# PulseOxi.net
KiCad netlist of a schematic drawn in EAGLE
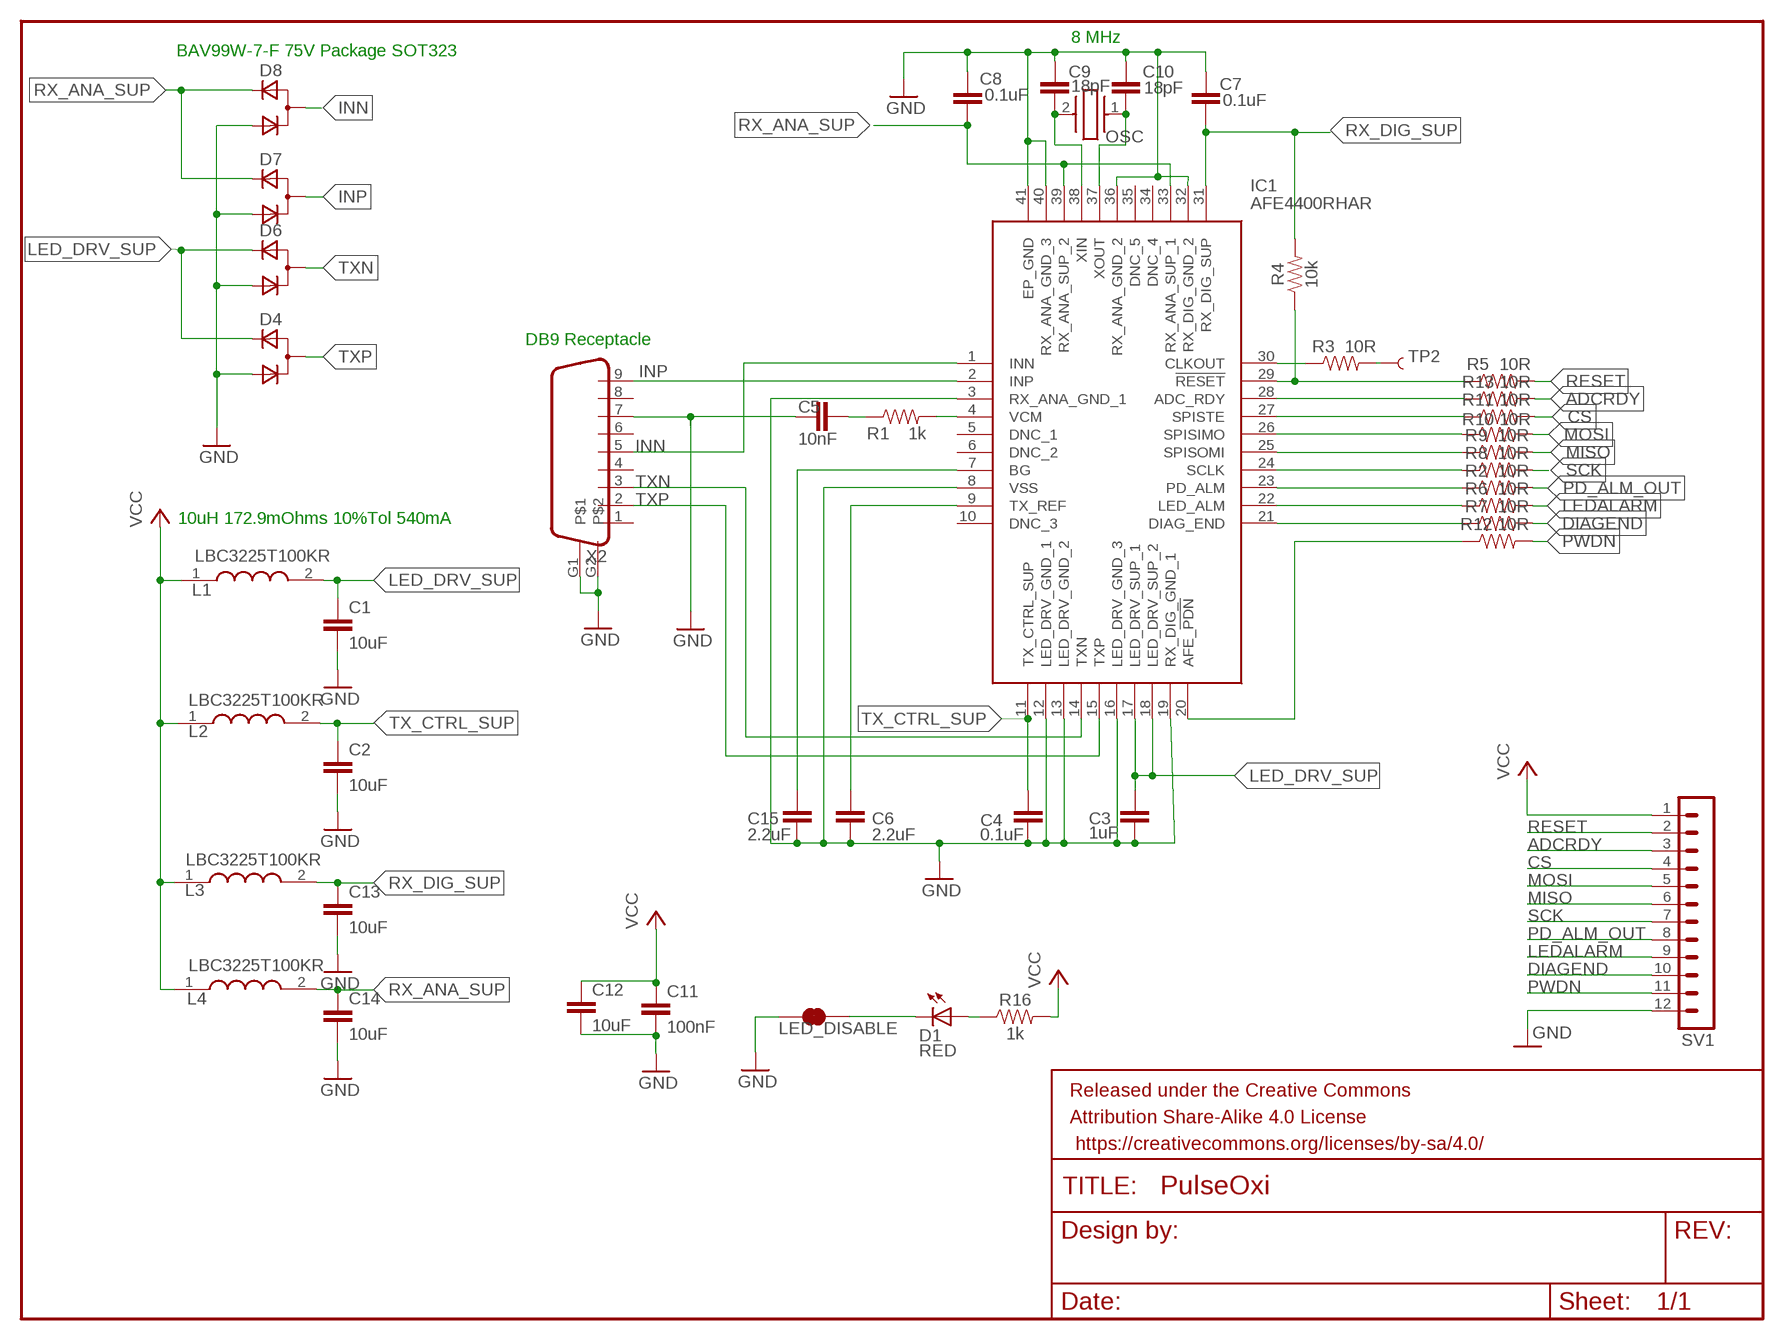
[diagram p0: schematic, sheet 1]

(export (version "E")
  (design (tool "Eeschema 10.0.6"))
  (components
    (comp (ref "C1")
      (value "10uF")
      (footprint "eagle-import:0603")
      (libsource (lib "eagle-import") (part "27PF-0603-50V-5%"))
    )
    (comp (ref "C2")
      (value "10uF")
      (footprint "eagle-import:0603")
      (libsource (lib "eagle-import") (part "27PF-0603-50V-5%"))
    )
    (comp (ref "C3")
      (value "1uF")
      (footprint "eagle-import:0603")
      (libsource (lib "eagle-import") (part "27PF-0603-50V-5%"))
    )
    (comp (ref "C4")
      (value "0.1uF")
      (footprint "eagle-import:0603")
      (libsource (lib "eagle-import") (part "27PF-0603-50V-5%"))
    )
    (comp (ref "C5")
      (value "10nF")
      (footprint "eagle-import:0603")
      (libsource (lib "eagle-import") (part "10NF-0603-50V-10%"))
    )
    (comp (ref "C6")
      (value "2.2uF")
      (footprint "eagle-import:0603")
      (libsource (lib "eagle-import") (part "27PF-0603-50V-5%"))
    )
    (comp (ref "C7")
      (value "0.1uF")
      (footprint "eagle-import:0603")
      (libsource (lib "eagle-import") (part "27PF-0603-50V-5%"))
    )
    (comp (ref "C8")
      (value "0.1uF")
      (footprint "eagle-import:0603")
      (libsource (lib "eagle-import") (part "27PF-0603-50V-5%"))
    )
    (comp (ref "C9")
      (value "18pF")
      (footprint "eagle-import:0603")
      (libsource (lib "eagle-import") (part "18PF-0603-50V-5%"))
    )
    (comp (ref "C10")
      (value "18pF")
      (footprint "eagle-import:0603")
      (libsource (lib "eagle-import") (part "18PF-0603-50V-5%"))
    )
    (comp (ref "C11")
      (value "100nF")
      (footprint "eagle-import:0603")
      (libsource (lib "eagle-import") (part "27PF-0603-50V-5%"))
    )
    (comp (ref "C12")
      (value "10uF")
      (footprint "eagle-import:0603")
      (libsource (lib "eagle-import") (part "27PF-0603-50V-5%"))
    )
    (comp (ref "C13")
      (value "10uF")
      (footprint "eagle-import:0603")
      (libsource (lib "eagle-import") (part "27PF-0603-50V-5%"))
    )
    (comp (ref "C14")
      (value "10uF")
      (footprint "eagle-import:0603")
      (libsource (lib "eagle-import") (part "27PF-0603-50V-5%"))
    )
    (comp (ref "C15")
      (value "2.2uF")
      (footprint "eagle-import:0603")
      (libsource (lib "eagle-import") (part "27PF-0603-50V-5%"))
    )
    (comp (ref "D1")
      (value "RED")
      (footprint "eagle-import:LED-0603")
      (libsource (lib "eagle-import") (part "LED-RED0603"))
    )
    (comp (ref "D4")
      (value "D_ACACSOT323")
      (footprint "eagle-import:SOT323")
      (libsource (lib "eagle-import") (part "D_ACACSOT323"))
    )
    (comp (ref "D6")
      (value "D_ACACSOT323")
      (footprint "eagle-import:SOT323")
      (libsource (lib "eagle-import") (part "D_ACACSOT323"))
    )
    (comp (ref "D7")
      (value "D_ACACSOT323")
      (footprint "eagle-import:SOT323")
      (libsource (lib "eagle-import") (part "D_ACACSOT323"))
    )
    (comp (ref "D8")
      (value "D_ACACSOT323")
      (footprint "eagle-import:SOT323")
      (libsource (lib "eagle-import") (part "D_ACACSOT323"))
    )
    (comp (ref "FRAME1")
      (value "FRAME-LETTERNO_PACKAGE")
      (footprint "eagle-import:DUMMY")
      (fields (field (name "DESIGNER") "Nobody"))
      (libsource (lib "eagle-import") (part "FRAME-LETTERNO_PACKAGE"))
    )
    (comp (ref "IC1")
      (value "AFE4400RHAR")
      (footprint "eagle-import:QFN50P600X600X100-41N")
      (fields (field (name "MOUSER_PART_NUMBER") "595-AFE4400RHAR"))
      (libsource (lib "eagle-import") (part "AFE4400RHAR"))
    )
    (comp (ref "L1")
      (value "LBC3225T100KR")
      (footprint "eagle-import:INDC3225X270N")
      (fields (field (name "MOUSER_PART_NUMBER") "963-LBC3225T100KR"))
      (libsource (lib "eagle-import") (part "LBC3225T100KR"))
    )
    (comp (ref "L2")
      (value "LBC3225T100KR")
      (footprint "eagle-import:INDC3225X270N")
      (fields (field (name "MOUSER_PART_NUMBER") "963-LBC3225T100KR"))
      (libsource (lib "eagle-import") (part "LBC3225T100KR"))
    )
    (comp (ref "L3")
      (value "LBC3225T100KR")
      (footprint "eagle-import:INDC3225X270N")
      (fields (field (name "MOUSER_PART_NUMBER") "963-LBC3225T100KR"))
      (libsource (lib "eagle-import") (part "LBC3225T100KR"))
    )
    (comp (ref "L4")
      (value "LBC3225T100KR")
      (footprint "eagle-import:INDC3225X270N")
      (fields (field (name "MOUSER_PART_NUMBER") "963-LBC3225T100KR"))
      (libsource (lib "eagle-import") (part "LBC3225T100KR"))
    )
    (comp (ref "LED_DISABLE")
      (value "JUMPER-SMT_2_NC_TRACE_SILK")
      (footprint "eagle-import:SMT-JUMPER_2_NC_TRACE_SILK")
      (libsource (lib "eagle-import") (part "JUMPER-SMT_2_NC_TRACE_SILK"))
    )
    (comp (ref "OSC")
      (value "ABM3-8.000MHZ-D2Y-T")
      (footprint "eagle-import:ABM3")
      (fields (field (name "MOUSER_PART_NUMBER") "815-ABM3-8-D2Y-T"))
      (libsource (lib "eagle-import") (part "ABM3-8.000MHZ-D2Y-T"))
    )
    (comp (ref "R1")
      (value "1k")
      (footprint "eagle-import:0603")
      (libsource (lib "eagle-import") (part "1KOHM-0603-1/10W-1%"))
    )
    (comp (ref "R2")
      (value "10R")
      (footprint "eagle-import:0603")
      (libsource (lib "eagle-import") (part "1.8MOHM"))
    )
    (comp (ref "R3")
      (value "10R")
      (footprint "eagle-import:0603")
      (libsource (lib "eagle-import") (part "1.8MOHM"))
    )
    (comp (ref "R4")
      (value "10k")
      (footprint "eagle-import:0603")
      (libsource (lib "eagle-import") (part "1.8MOHM"))
    )
    (comp (ref "R5")
      (value "10R")
      (footprint "eagle-import:0603")
      (libsource (lib "eagle-import") (part "1.8MOHM"))
    )
    (comp (ref "R6")
      (value "10R")
      (footprint "eagle-import:0603")
      (libsource (lib "eagle-import") (part "1.8MOHM"))
    )
    (comp (ref "R7")
      (value "10R")
      (footprint "eagle-import:0603")
      (libsource (lib "eagle-import") (part "1.8MOHM"))
    )
    (comp (ref "R8")
      (value "10R")
      (footprint "eagle-import:0603")
      (libsource (lib "eagle-import") (part "1.8MOHM"))
    )
    (comp (ref "R9")
      (value "10R")
      (footprint "eagle-import:0603")
      (libsource (lib "eagle-import") (part "1.8MOHM"))
    )
    (comp (ref "R10")
      (value "10R")
      (footprint "eagle-import:0603")
      (libsource (lib "eagle-import") (part "1.8MOHM"))
    )
    (comp (ref "R11")
      (value "10R")
      (footprint "eagle-import:0603")
      (libsource (lib "eagle-import") (part "1.8MOHM"))
    )
    (comp (ref "R12")
      (value "10R")
      (footprint "eagle-import:0603")
      (libsource (lib "eagle-import") (part "1.8MOHM"))
    )
    (comp (ref "R13")
      (value "10R")
      (footprint "eagle-import:0603")
      (libsource (lib "eagle-import") (part "1.8MOHM"))
    )
    (comp (ref "R16")
      (value "1k")
      (footprint "eagle-import:0603")
      (libsource (lib "eagle-import") (part "1KOHM-0603-1/10W-1%"))
    )
    (comp (ref "SV1")
      (value "MA12-1")
      (footprint "eagle-import:MA12-1")
      (libsource (lib "eagle-import") (part "MA12-1"))
    )
    (comp (ref "TP2")
      (value "TEST-POINT3")
      (footprint "eagle-import:PAD.03X.03")
      (libsource (lib "eagle-import") (part "TEST-POINT3"))
    )
    (comp (ref "X2")
      (value "DB9")
      (footprint "eagle-import:DB9")
      (libsource (lib "eagle-import") (part "DB9"))
    )
  )
  (nets
    (net (code "1") (name "ADCRDY") (class "Default")
      (node (ref "R13") (pin "2") (pinfunction "2_2") (pintype "passive"))
      (node (ref "SV1") (pin "3") (pinfunction "3_3") (pintype "passive"))
    )
    (net (code "2") (name "CS") (class "Default")
      (node (ref "R11") (pin "2") (pinfunction "2_2") (pintype "passive"))
      (node (ref "SV1") (pin "4") (pinfunction "4_4") (pintype "passive"))
    )
    (net (code "3") (name "DIAGEND") (class "Default")
      (node (ref "R7") (pin "2") (pinfunction "2_2") (pintype "passive"))
      (node (ref "SV1") (pin "10") (pinfunction "10_10") (pintype "passive"))
    )
    (net (code "4") (name "GND") (class "Default")
      (node (ref "C1") (pin "2") (pinfunction "2_2") (pintype "passive"))
      (node (ref "C10") (pin "2") (pinfunction "2_2") (pintype "passive"))
      (node (ref "C11") (pin "2") (pinfunction "2_2") (pintype "passive"))
      (node (ref "C12") (pin "2") (pinfunction "2_2") (pintype "passive"))
      (node (ref "C13") (pin "2") (pinfunction "2_2") (pintype "passive"))
      (node (ref "C14") (pin "2") (pinfunction "2_2") (pintype "passive"))
      (node (ref "C15") (pin "2") (pinfunction "2_2") (pintype "passive"))
      (node (ref "C2") (pin "2") (pinfunction "2_2") (pintype "passive"))
      (node (ref "C3") (pin "2") (pinfunction "2_2") (pintype "passive"))
      (node (ref "C4") (pin "2") (pinfunction "2_2") (pintype "passive"))
      (node (ref "C5") (pin "2") (pinfunction "2_2") (pintype "passive"))
      (node (ref "C6") (pin "2") (pinfunction "2_2") (pintype "passive"))
      (node (ref "C7") (pin "2") (pinfunction "2_2") (pintype "passive"))
      (node (ref "C8") (pin "2") (pinfunction "2_2") (pintype "passive"))
      (node (ref "C9") (pin "2") (pinfunction "2_2") (pintype "passive"))
      (node (ref "D4") (pin "2") (pinfunction "C_2") (pintype "passive"))
      (node (ref "D6") (pin "2") (pinfunction "C_2") (pintype "passive"))
      (node (ref "D7") (pin "2") (pinfunction "C_2") (pintype "passive"))
      (node (ref "D8") (pin "2") (pinfunction "C_2") (pintype "passive"))
      (node (ref "IC1") (pin "12") (pinfunction "LED_DRV_GND_1_12") (pintype "power_in"))
      (node (ref "IC1") (pin "13") (pinfunction "LED_DRV_GND_2_13") (pintype "power_in"))
      (node (ref "IC1") (pin "16") (pinfunction "LED_DRV_GND_3_16") (pintype "power_in"))
      (node (ref "IC1") (pin "19") (pinfunction "RX_DIG_GND_1_19") (pintype "power_in"))
      (node (ref "IC1") (pin "3") (pinfunction "RX_ANA_GND_1_3") (pintype "power_in"))
      (node (ref "IC1") (pin "32") (pinfunction "RX_DIG_GND_2_32") (pintype "power_in"))
      (node (ref "IC1") (pin "36") (pinfunction "RX_ANA_GND_2_36") (pintype "power_in"))
      (node (ref "IC1") (pin "40") (pinfunction "RX_ANA_GND_3_40") (pintype "power_in"))
      (node (ref "IC1") (pin "41") (pinfunction "EP_GND_41") (pintype "power_in"))
      (node (ref "IC1") (pin "8") (pinfunction "VSS_8") (pintype "power_in"))
      (node (ref "LED_DISABLE") (pin "1") (pinfunction "1_1") (pintype "passive"))
      (node (ref "SV1") (pin "12") (pinfunction "12_12") (pintype "passive"))
      (node (ref "X2") (pin "7") (pinfunction "7_7") (pintype "passive"))
      (node (ref "X2") (pin "G1") (pinfunction "P$1_G1") (pintype "bidirectional"))
      (node (ref "X2") (pin "G2") (pinfunction "P$2_G2") (pintype "bidirectional"))
    )
    (net (code "5") (name "INN") (class "Default")
      (node (ref "D8") (pin "1") (pinfunction "CA_1") (pintype "passive"))
      (node (ref "IC1") (pin "1") (pinfunction "INN_1") (pintype "input"))
      (node (ref "X2") (pin "5") (pinfunction "5_5") (pintype "passive"))
    )
    (net (code "6") (name "INP") (class "Default")
      (node (ref "D7") (pin "1") (pinfunction "CA_1") (pintype "passive"))
      (node (ref "IC1") (pin "2") (pinfunction "INP_2") (pintype "input"))
      (node (ref "X2") (pin "9") (pinfunction "9_9") (pintype "passive"))
    )
    (net (code "7") (name "LEDALARM") (class "Default")
      (node (ref "R6") (pin "2") (pinfunction "2_2") (pintype "passive"))
      (node (ref "SV1") (pin "9") (pinfunction "9_9") (pintype "passive"))
    )
    (net (code "8") (name "LED_DRV_SUP") (class "Default")
      (node (ref "C1") (pin "1") (pinfunction "1_1") (pintype "passive"))
      (node (ref "C3") (pin "1") (pinfunction "1_1") (pintype "passive"))
      (node (ref "D4") (pin "3") (pinfunction "A_3") (pintype "passive"))
      (node (ref "D6") (pin "3") (pinfunction "A_3") (pintype "passive"))
      (node (ref "IC1") (pin "17") (pinfunction "LED_DRV_SUP_1_17") (pintype "bidirectional"))
      (node (ref "IC1") (pin "18") (pinfunction "LED_DRV_SUP_2_18") (pintype "bidirectional"))
      (node (ref "L1") (pin "2") (pinfunction "2_2") (pintype "bidirectional"))
    )
    (net (code "9") (name "MISO") (class "Default")
      (node (ref "R9") (pin "2") (pinfunction "2_2") (pintype "passive"))
      (node (ref "SV1") (pin "6") (pinfunction "6_6") (pintype "passive"))
    )
    (net (code "10") (name "MOSI") (class "Default")
      (node (ref "R10") (pin "2") (pinfunction "2_2") (pintype "passive"))
      (node (ref "SV1") (pin "5") (pinfunction "5_5") (pintype "passive"))
    )
    (net (code "11") (name "Net-(C5-Pad1)") (class "Default")
      (node (ref "C5") (pin "1") (pinfunction "1_1") (pintype "passive"))
      (node (ref "R1") (pin "1") (pinfunction "1_1") (pintype "passive"))
    )
    (net (code "12") (name "Net-(D1-PadA)") (class "Default")
      (node (ref "D1") (pin "A") (pinfunction "A_A") (pintype "passive"))
      (node (ref "R16") (pin "1") (pinfunction "1_1") (pintype "passive"))
    )
    (net (code "13") (name "Net-(D1-PadC)") (class "Default")
      (node (ref "D1") (pin "C") (pinfunction "C_C") (pintype "passive"))
      (node (ref "LED_DISABLE") (pin "2") (pinfunction "2_2") (pintype "passive"))
    )
    (net (code "14") (name "Net-(IC1-ADC_RDY)") (class "Default")
      (node (ref "IC1") (pin "28") (pinfunction "ADC_RDY_28") (pintype "bidirectional"))
      (node (ref "R13") (pin "1") (pinfunction "1_1") (pintype "passive"))
    )
    (net (code "15") (name "Net-(IC1-AFE_~{PDN})") (class "Default")
      (node (ref "IC1") (pin "20") (pinfunction "AFE_~{PDN}_20") (pintype "bidirectional"))
      (node (ref "R12") (pin "1") (pinfunction "1_1") (pintype "passive"))
    )
    (net (code "16") (name "Net-(IC1-BG)") (class "Default")
      (node (ref "C15") (pin "1") (pinfunction "1_1") (pintype "passive"))
      (node (ref "IC1") (pin "7") (pinfunction "BG_7") (pintype "bidirectional"))
    )
    (net (code "17") (name "Net-(IC1-CLKOUT)") (class "Default")
      (node (ref "IC1") (pin "30") (pinfunction "CLKOUT_30") (pintype "output"))
      (node (ref "R3") (pin "1") (pinfunction "1_1") (pintype "passive"))
    )
    (net (code "18") (name "Net-(IC1-DIAG_END)") (class "Default")
      (node (ref "IC1") (pin "21") (pinfunction "DIAG_END_21") (pintype "bidirectional"))
      (node (ref "R7") (pin "1") (pinfunction "1_1") (pintype "passive"))
    )
    (net (code "19") (name "Net-(IC1-LED_ALM)") (class "Default")
      (node (ref "IC1") (pin "22") (pinfunction "LED_ALM_22") (pintype "bidirectional"))
      (node (ref "R6") (pin "1") (pinfunction "1_1") (pintype "passive"))
    )
    (net (code "20") (name "Net-(IC1-PD_ALM)") (class "Default")
      (node (ref "IC1") (pin "23") (pinfunction "PD_ALM_23") (pintype "bidirectional"))
      (node (ref "R2") (pin "1") (pinfunction "1_1") (pintype "passive"))
    )
    (net (code "21") (name "Net-(IC1-SCLK)") (class "Default")
      (node (ref "IC1") (pin "24") (pinfunction "SCLK_24") (pintype "input"))
      (node (ref "R8") (pin "1") (pinfunction "1_1") (pintype "passive"))
    )
    (net (code "22") (name "Net-(IC1-SPISIMO)") (class "Default")
      (node (ref "IC1") (pin "26") (pinfunction "SPISIMO_26") (pintype "bidirectional"))
      (node (ref "R10") (pin "1") (pinfunction "1_1") (pintype "passive"))
    )
    (net (code "23") (name "Net-(IC1-SPISOMI)") (class "Default")
      (node (ref "IC1") (pin "25") (pinfunction "SPISOMI_25") (pintype "bidirectional"))
      (node (ref "R9") (pin "1") (pinfunction "1_1") (pintype "passive"))
    )
    (net (code "24") (name "Net-(IC1-SPISTE)") (class "Default")
      (node (ref "IC1") (pin "27") (pinfunction "SPISTE_27") (pintype "bidirectional"))
      (node (ref "R11") (pin "1") (pinfunction "1_1") (pintype "passive"))
    )
    (net (code "25") (name "Net-(IC1-TX_REF)") (class "Default")
      (node (ref "C6") (pin "1") (pinfunction "1_1") (pintype "passive"))
      (node (ref "IC1") (pin "9") (pinfunction "TX_REF_9") (pintype "input"))
    )
    (net (code "26") (name "Net-(IC1-VCM)") (class "Default")
      (node (ref "IC1") (pin "4") (pinfunction "VCM_4") (pintype "bidirectional"))
      (node (ref "R1") (pin "2") (pinfunction "2_2") (pintype "passive"))
    )
    (net (code "27") (name "Net-(IC1-XIN)") (class "Default")
      (node (ref "C9") (pin "1") (pinfunction "1_1") (pintype "passive"))
      (node (ref "IC1") (pin "38") (pinfunction "XIN_38") (pintype "input"))
      (node (ref "OSC") (pin "2") (pinfunction "2_2") (pintype "bidirectional"))
    )
    (net (code "28") (name "Net-(IC1-XOUT)") (class "Default")
      (node (ref "C10") (pin "1") (pinfunction "1_1") (pintype "passive"))
      (node (ref "IC1") (pin "37") (pinfunction "XOUT_37") (pintype "output"))
      (node (ref "OSC") (pin "1") (pinfunction "1_1") (pintype "bidirectional"))
    )
    (net (code "29") (name "Net-(IC1-~{RESET})") (class "Default")
      (node (ref "IC1") (pin "29") (pinfunction "~{RESET}_29") (pintype "bidirectional"))
      (node (ref "R4") (pin "1") (pinfunction "1_1") (pintype "passive"))
      (node (ref "R5") (pin "1") (pinfunction "1_1") (pintype "passive"))
    )
    (net (code "30") (name "Net-(TP2-1)") (class "Default")
      (node (ref "R3") (pin "2") (pinfunction "2_2") (pintype "passive"))
      (node (ref "TP2") (pin "P$1") (pinfunction "1_P$1") (pintype "bidirectional"))
    )
    (net (code "31") (name "PD_ALM_OUT") (class "Default")
      (node (ref "R2") (pin "2") (pinfunction "2_2") (pintype "passive"))
      (node (ref "SV1") (pin "8") (pinfunction "8_8") (pintype "passive"))
    )
    (net (code "32") (name "PWDN") (class "Default")
      (node (ref "R12") (pin "2") (pinfunction "2_2") (pintype "passive"))
      (node (ref "SV1") (pin "11") (pinfunction "11_11") (pintype "passive"))
    )
    (net (code "33") (name "RESET") (class "Default")
      (node (ref "R5") (pin "2") (pinfunction "2_2") (pintype "passive"))
      (node (ref "SV1") (pin "2") (pinfunction "2_2") (pintype "passive"))
    )
    (net (code "34") (name "RX_ANA_SUP") (class "Default")
      (node (ref "C14") (pin "1") (pinfunction "1_1") (pintype "passive"))
      (node (ref "C8") (pin "1") (pinfunction "1_1") (pintype "passive"))
      (node (ref "D7") (pin "3") (pinfunction "A_3") (pintype "passive"))
      (node (ref "D8") (pin "3") (pinfunction "A_3") (pintype "passive"))
      (node (ref "IC1") (pin "33") (pinfunction "RX_ANA_SUP_1_33") (pintype "bidirectional"))
      (node (ref "IC1") (pin "39") (pinfunction "RX_ANA_SUP_2_39") (pintype "bidirectional"))
      (node (ref "L4") (pin "2") (pinfunction "2_2") (pintype "bidirectional"))
    )
    (net (code "35") (name "RX_DIG_SUP") (class "Default")
      (node (ref "C13") (pin "1") (pinfunction "1_1") (pintype "passive"))
      (node (ref "C7") (pin "1") (pinfunction "1_1") (pintype "passive"))
      (node (ref "IC1") (pin "31") (pinfunction "RX_DIG_SUP_31") (pintype "bidirectional"))
      (node (ref "L3") (pin "2") (pinfunction "2_2") (pintype "bidirectional"))
      (node (ref "R4") (pin "2") (pinfunction "2_2") (pintype "passive"))
    )
    (net (code "36") (name "SCK") (class "Default")
      (node (ref "R8") (pin "2") (pinfunction "2_2") (pintype "passive"))
      (node (ref "SV1") (pin "7") (pinfunction "7_7") (pintype "passive"))
    )
    (net (code "37") (name "TXN") (class "Default")
      (node (ref "D6") (pin "1") (pinfunction "CA_1") (pintype "passive"))
      (node (ref "IC1") (pin "14") (pinfunction "TXN_14") (pintype "bidirectional"))
      (node (ref "X2") (pin "3") (pinfunction "3_3") (pintype "passive"))
    )
    (net (code "38") (name "TXP") (class "Default")
      (node (ref "D4") (pin "1") (pinfunction "CA_1") (pintype "passive"))
      (node (ref "IC1") (pin "15") (pinfunction "TXP_15") (pintype "bidirectional"))
      (node (ref "X2") (pin "2") (pinfunction "2_2") (pintype "passive"))
    )
    (net (code "39") (name "TX_CTRL_SUP") (class "Default")
      (node (ref "C2") (pin "1") (pinfunction "1_1") (pintype "passive"))
      (node (ref "C4") (pin "1") (pinfunction "1_1") (pintype "passive"))
      (node (ref "IC1") (pin "11") (pinfunction "TX_CTRL_SUP_11") (pintype "bidirectional"))
      (node (ref "L2") (pin "2") (pinfunction "2_2") (pintype "bidirectional"))
    )
    (net (code "40") (name "VCC") (class "Default")
      (node (ref "C11") (pin "1") (pinfunction "1_1") (pintype "passive"))
      (node (ref "C12") (pin "1") (pinfunction "1_1") (pintype "passive"))
      (node (ref "L1") (pin "1") (pinfunction "1_1") (pintype "bidirectional"))
      (node (ref "L2") (pin "1") (pinfunction "1_1") (pintype "bidirectional"))
      (node (ref "L3") (pin "1") (pinfunction "1_1") (pintype "bidirectional"))
      (node (ref "L4") (pin "1") (pinfunction "1_1") (pintype "bidirectional"))
      (node (ref "R16") (pin "2") (pinfunction "2_2") (pintype "passive"))
      (node (ref "SV1") (pin "1") (pinfunction "1_1") (pintype "passive"))
    )
    (net (code "41") (name "unconnected-(IC1-DNC_1-Pad5)") (class "Default")
      (node (ref "IC1") (pin "5") (pinfunction "DNC_1_5") (pintype "bidirectional"))
    )
    (net (code "42") (name "unconnected-(IC1-DNC_2-Pad6)") (class "Default")
      (node (ref "IC1") (pin "6") (pinfunction "DNC_2_6") (pintype "bidirectional"))
    )
    (net (code "43") (name "unconnected-(IC1-DNC_3-Pad10)") (class "Default")
      (node (ref "IC1") (pin "10") (pinfunction "DNC_3_10") (pintype "bidirectional"))
    )
    (net (code "44") (name "unconnected-(IC1-DNC_4-Pad34)") (class "Default")
      (node (ref "IC1") (pin "34") (pinfunction "DNC_4_34") (pintype "bidirectional"))
    )
    (net (code "45") (name "unconnected-(IC1-DNC_5-Pad35)") (class "Default")
      (node (ref "IC1") (pin "35") (pinfunction "DNC_5_35") (pintype "bidirectional"))
    )
    (net (code "46") (name "unconnected-(X2-Pad1)") (class "Default")
      (node (ref "X2") (pin "1") (pinfunction "1_1") (pintype "passive"))
    )
    (net (code "47") (name "unconnected-(X2-Pad4)") (class "Default")
      (node (ref "X2") (pin "4") (pinfunction "4_4") (pintype "passive"))
    )
    (net (code "48") (name "unconnected-(X2-Pad6)") (class "Default")
      (node (ref "X2") (pin "6") (pinfunction "6_6") (pintype "passive"))
    )
    (net (code "49") (name "unconnected-(X2-Pad8)") (class "Default")
      (node (ref "X2") (pin "8") (pinfunction "8_8") (pintype "passive"))
    )
  )
)
